# new_sheet.net
KiCad netlist of a schematic drawn in Altium Designer
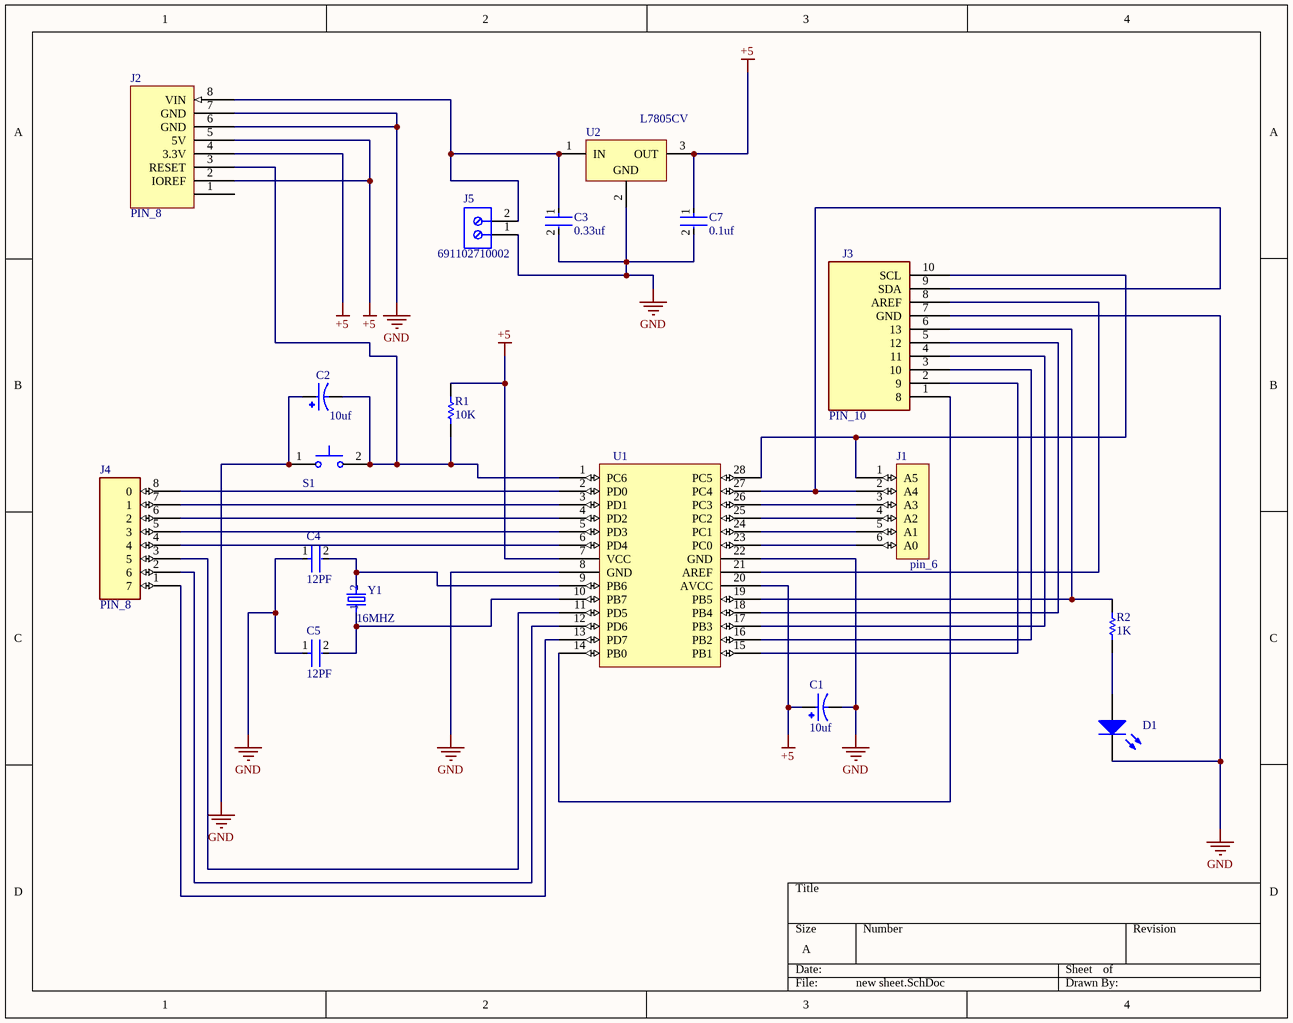
[diagram p0: new sheet.SchDoc]

(export (version "E")
  (design (tool "Eeschema 10.0.6"))
  (components
    (comp (ref "C1")
      (value "10uf")
      (footprint "PcbLib1:CAPPRD500W50D630H1120")
      (description "Cap Aluminum Lytic 10uF 100V 20% Radial 105C Automotive Ammo")
      (fields (field (name "MF") "Panasonic") (field (name "MP") "EEU-FC2A100B"))
      (libsource (lib "*") (part "EEUFC2A100B"))
    )
    (comp (ref "C2")
      (value "10uf")
      (footprint "PcbLib1:CAPPRD500W50D630H1120")
      (description "Cap Aluminum Lytic 10uF 100V 20% Radial 105C Automotive Ammo")
      (fields (field (name "MF") "Panasonic") (field (name "MP") "EEU-FC2A100B"))
      (libsource (lib "*") (part "EEUFC2A100B"))
    )
    (comp (ref "C3")
      (value "0.33uf")
      (footprint "FP-K15H5-MFG")
      (description "CAP CER 0.1UF 50V X7R RADIAL")
      (fields (field (name "TOLERANCE") "10%") (field (name "VOLTAGE") "50V"))
      (libsource (lib "Altium Content Vault") (part "02cd4be3c70576c341d710602a673aa"))
    )
    (comp (ref "C4")
      (value "12PF")
      (footprint "FP-K15H5-MFG")
      (description "CAP CER 0.1UF 50V X7R RADIAL")
      (fields (field (name "TOLERANCE") "10%") (field (name "VOLTAGE") "50V"))
      (libsource (lib "Altium Content Vault") (part "02cd4be3c70576c341d710602a673aa"))
    )
    (comp (ref "C5")
      (value "12PF")
      (footprint "FP-K15H5-MFG")
      (description "CAP CER 0.1UF 50V X7R RADIAL")
      (fields (field (name "TOLERANCE") "10%") (field (name "VOLTAGE") "50V"))
      (libsource (lib "Altium Content Vault") (part "02cd4be3c70576c341d710602a673aa"))
    )
    (comp (ref "C7")
      (value "0.1uf")
      (footprint "FP-K15H5-MFG")
      (description "CAP CER 0.1UF 50V X7R RADIAL")
      (fields (field (name "TOLERANCE") "10%") (field (name "VOLTAGE") "50V"))
      (libsource (lib "Altium Content Vault") (part "02cd4be3c70576c341d710602a673aa"))
    )
    (comp (ref "D1")
      (value "Light-Emitting Diode")
      (footprint "LED")
      (libsource (lib "Simulation Generic Components") (part "LED"))
    )
    (comp (ref "J1") (value "pin_6") (footprint "pin_6") (libsource (lib "*") (part "pin_6")))
    (comp (ref "J2") (value "PIN_8") (footprint "pin_8") (libsource (lib "*") (part "PIN_8")))
    (comp (ref "J3")
      (value "PIN_10")
      (footprint "pin_10")
      (fields
        (field (name "MANUFACTURER_PART_NUMBER") "22-23-2101")
        (field (name "MOUSER PART NUMBER") "538-22-23-2101")
      )
      (libsource (lib "*") (part "22-23-2101"))
    )
    (comp (ref "J4")
      (value "PIN_8")
      (footprint "pin_8")
      (description "Headers & Wire Housings 2.54MM PITCH SRSW T/H HEADER 8 CKT")
      (fields
        (field (name "MANUFACTURER_PART_NUMBER") "87891-0808")
        (field (name "MOUSER PART NUMBER") "538-87891-0808")
      )
      (libsource (lib "*") (part "PIN DIGITAL"))
    )
    (comp (ref "J5")
      (value "691102710002")
      (footprint "691102710002")
      (fields (field (name "VOLTAGE") "300V"))
      (libsource (lib "Altium Content Vault") (part "TBL - 1R - 02P - Screw"))
    )
    (comp (ref "R1")
      (value "10K")
      (footprint "RESISTANCE")
      (description "Resistor")
      (libsource (lib "Simulation Generic Components") (part "Resistor"))
    )
    (comp (ref "R2")
      (value "1K")
      (footprint "RESISTANCE")
      (description "Resistor")
      (libsource (lib "Simulation Generic Components") (part "Resistor"))
    )
    (comp (ref "S1")
      (value "~")
      (footprint "SW_BUTT-2")
      (description "Tactile Switches MINI PUSH BUTTON SWITCH 2-PIN QTY. 4")
      (fields (field (name "MF") "Gravitech") (field (name "MP") "BUTT-2"))
      (libsource (lib "*") (part "BUTT-2"))
    )
    (comp (ref "U1")
      (value "~")
      (footprint "DIP787W46P254L3467H508Q28")
      (libsource (lib "*") (part "atmega328p"))
    )
    (comp (ref "U2")
      (value "L7805CV")
      (footprint "TO220")
      (description "Positive Voltage Regulator, 5V, 3-Pin TO-220")
      (libsource (lib "Altium Content Vault") (part "PM-REG-L4940-SIL3"))
    )
    (comp (ref "Y1")
      (value "16MHZ")
      (footprint "XT9S20ANA16M")
      (description "Microprocessor, Crystal; 16 MHz; + 30 ppm _Typ._ @ 25 degC; 7 pF _Max._; 40 Ohm")
      (fields (field (name "MF") "Vishay Dale") (field (name "MP") "XT9S20ANA16M"))
      (libsource (lib "*") (part "XT9S20ANA16M"))
    )
  )
  (nets
    (net (code "1") (name "+5") (class "Default")
      (node (ref "C1") (pin "P") (pinfunction "P_P") (pintype "passive"))
      (node (ref "C7") (pin "1") (pinfunction "1_1") (pintype "passive"))
      (node (ref "J2") (pin "2") (pinfunction "IOREF_2") (pintype "power_in"))
      (node (ref "J2") (pin "4") (pinfunction "3.3V_4") (pintype "power_in"))
      (node (ref "J2") (pin "5") (pinfunction "5V_5") (pintype "power_in"))
      (node (ref "R1") (pin "2") (pinfunction "2_2") (pintype "passive"))
      (node (ref "U1") (pin "20") (pinfunction "AVCC_20") (pintype "power_in"))
      (node (ref "U1") (pin "7") (pinfunction "VCC_7") (pintype "power_in"))
      (node (ref "U2") (pin "3") (pinfunction "OUT_3") (pintype "power_in"))
    )
    (net (code "2") (name "GND") (class "Default")
      (node (ref "C1") (pin "N") (pinfunction "N_N") (pintype "passive"))
      (node (ref "C2") (pin "P") (pinfunction "P_P") (pintype "passive"))
      (node (ref "C3") (pin "2") (pinfunction "2_2") (pintype "passive"))
      (node (ref "C4") (pin "1") (pinfunction "1_1") (pintype "passive"))
      (node (ref "C5") (pin "1") (pinfunction "1_1") (pintype "passive"))
      (node (ref "C7") (pin "2") (pinfunction "2_2") (pintype "passive"))
      (node (ref "D1") (pin "2") (pinfunction "K_2") (pintype "passive"))
      (node (ref "J2") (pin "6") (pinfunction "GND_6") (pintype "power_in"))
      (node (ref "J2") (pin "7") (pinfunction "GND_7") (pintype "power_in"))
      (node (ref "J3") (pin "7") (pinfunction "GND_7") (pintype "passive"))
      (node (ref "J5") (pin "1") (pinfunction "1_1") (pintype "passive"))
      (node (ref "S1") (pin "1") (pinfunction "1_1") (pintype "passive"))
      (node (ref "U1") (pin "22") (pinfunction "GND_22") (pintype "power_in"))
      (node (ref "U1") (pin "8") (pinfunction "GND_8") (pintype "power_in"))
      (node (ref "U2") (pin "2") (pinfunction "GND_2") (pintype "power_in"))
    )
    (net (code "3") (name "Net-(D1-A)") (class "Default")
      (node (ref "D1") (pin "1") (pinfunction "A_1") (pintype "passive"))
      (node (ref "R2") (pin "1") (pinfunction "1_1") (pintype "passive"))
    )
    (net (code "4") (name "Net-(J1-A0)") (class "Default")
      (node (ref "J1") (pin "6") (pinfunction "A0_6") (pintype "bidirectional"))
      (node (ref "U1") (pin "23") (pinfunction "PC0_23") (pintype "bidirectional"))
    )
    (net (code "5") (name "Net-(J1-A1)") (class "Default")
      (node (ref "J1") (pin "5") (pinfunction "A1_5") (pintype "bidirectional"))
      (node (ref "U1") (pin "24") (pinfunction "PC1_24") (pintype "bidirectional"))
    )
    (net (code "6") (name "Net-(J1-A2)") (class "Default")
      (node (ref "J1") (pin "4") (pinfunction "A2_4") (pintype "bidirectional"))
      (node (ref "U1") (pin "25") (pinfunction "PC2_25") (pintype "bidirectional"))
    )
    (net (code "7") (name "Net-(J1-A3)") (class "Default")
      (node (ref "J1") (pin "3") (pinfunction "A3_3") (pintype "bidirectional"))
      (node (ref "U1") (pin "26") (pinfunction "PC3_26") (pintype "bidirectional"))
    )
    (net (code "8") (name "Net-(J1-A4)") (class "Default")
      (node (ref "J1") (pin "2") (pinfunction "A4_2") (pintype "bidirectional"))
      (node (ref "J3") (pin "9") (pinfunction "SDA_9") (pintype "passive"))
      (node (ref "U1") (pin "27") (pinfunction "PC4_27") (pintype "bidirectional"))
    )
    (net (code "9") (name "Net-(J1-A5)") (class "Default")
      (node (ref "J1") (pin "1") (pinfunction "A5_1") (pintype "bidirectional"))
      (node (ref "J3") (pin "10") (pinfunction "SCL_10") (pintype "passive"))
      (node (ref "U1") (pin "28") (pinfunction "PC5_28") (pintype "bidirectional"))
    )
    (net (code "10") (name "Net-(J2-RESET)") (class "Default")
      (node (ref "C2") (pin "N") (pinfunction "N_N") (pintype "passive"))
      (node (ref "J2") (pin "3") (pinfunction "RESET_3") (pintype "passive"))
      (node (ref "R1") (pin "1") (pinfunction "1_1") (pintype "passive"))
      (node (ref "S1") (pin "2") (pinfunction "2_2") (pintype "passive"))
      (node (ref "U1") (pin "1") (pinfunction "PC6_1") (pintype "bidirectional"))
    )
    (net (code "11") (name "Net-(J2-VIN)") (class "Default")
      (node (ref "C3") (pin "1") (pinfunction "1_1") (pintype "passive"))
      (node (ref "J2") (pin "8") (pinfunction "VIN_8") (pintype "input"))
      (node (ref "J5") (pin "2") (pinfunction "2_2") (pintype "passive"))
      (node (ref "U2") (pin "1") (pinfunction "IN_1") (pintype "power_in"))
    )
    (net (code "12") (name "Net-(J3-8)") (class "Default")
      (node (ref "J3") (pin "1") (pinfunction "8_1") (pintype "passive"))
      (node (ref "U1") (pin "14") (pinfunction "PB0_14") (pintype "bidirectional"))
    )
    (net (code "13") (name "Net-(J3-9)") (class "Default")
      (node (ref "J3") (pin "2") (pinfunction "9_2") (pintype "passive"))
      (node (ref "U1") (pin "15") (pinfunction "PB1_15") (pintype "bidirectional"))
    )
    (net (code "14") (name "Net-(J3-10)") (class "Default")
      (node (ref "J3") (pin "3") (pinfunction "10_3") (pintype "passive"))
      (node (ref "U1") (pin "16") (pinfunction "PB2_16") (pintype "bidirectional"))
    )
    (net (code "15") (name "Net-(J3-11)") (class "Default")
      (node (ref "J3") (pin "4") (pinfunction "11_4") (pintype "passive"))
      (node (ref "U1") (pin "17") (pinfunction "PB3_17") (pintype "bidirectional"))
    )
    (net (code "16") (name "Net-(J3-12)") (class "Default")
      (node (ref "J3") (pin "5") (pinfunction "12_5") (pintype "passive"))
      (node (ref "U1") (pin "18") (pinfunction "PB4_18") (pintype "bidirectional"))
    )
    (net (code "17") (name "Net-(J3-13)") (class "Default")
      (node (ref "J3") (pin "6") (pinfunction "13_6") (pintype "passive"))
      (node (ref "R2") (pin "2") (pinfunction "2_2") (pintype "passive"))
      (node (ref "U1") (pin "19") (pinfunction "PB5_19") (pintype "bidirectional"))
    )
    (net (code "18") (name "Net-(J3-AREF)") (class "Default")
      (node (ref "J3") (pin "8") (pinfunction "AREF_8") (pintype "passive"))
      (node (ref "U1") (pin "21") (pinfunction "AREF_21") (pintype "power_in"))
    )
    (net (code "19") (name "Net-(J4-0)") (class "Default")
      (node (ref "J4") (pin "8") (pinfunction "0_8") (pintype "bidirectional"))
      (node (ref "U1") (pin "2") (pinfunction "PD0_2") (pintype "bidirectional"))
    )
    (net (code "20") (name "Net-(J4-1)") (class "Default")
      (node (ref "J4") (pin "7") (pinfunction "1_7") (pintype "bidirectional"))
      (node (ref "U1") (pin "3") (pinfunction "PD1_3") (pintype "bidirectional"))
    )
    (net (code "21") (name "Net-(J4-2)") (class "Default")
      (node (ref "J4") (pin "6") (pinfunction "2_6") (pintype "bidirectional"))
      (node (ref "U1") (pin "4") (pinfunction "PD2_4") (pintype "bidirectional"))
    )
    (net (code "22") (name "Net-(J4-3)") (class "Default")
      (node (ref "J4") (pin "5") (pinfunction "3_5") (pintype "bidirectional"))
      (node (ref "U1") (pin "5") (pinfunction "PD3_5") (pintype "bidirectional"))
    )
    (net (code "23") (name "Net-(J4-5)") (class "Default")
      (node (ref "J4") (pin "3") (pinfunction "5_3") (pintype "bidirectional"))
      (node (ref "U1") (pin "11") (pinfunction "PD5_11") (pintype "bidirectional"))
    )
    (net (code "24") (name "Net-(J4-6)") (class "Default")
      (node (ref "J4") (pin "2") (pinfunction "6_2") (pintype "bidirectional"))
      (node (ref "U1") (pin "12") (pinfunction "PD6_12") (pintype "bidirectional"))
    )
    (net (code "25") (name "Net-(J4-7)") (class "Default")
      (node (ref "J4") (pin "1") (pinfunction "7_1") (pintype "bidirectional"))
      (node (ref "U1") (pin "13") (pinfunction "PD7_13") (pintype "bidirectional"))
    )
    (net (code "26") (name "Net-(U1-PB6)") (class "Default")
      (node (ref "C4") (pin "2") (pinfunction "2_2") (pintype "passive"))
      (node (ref "U1") (pin "9") (pinfunction "PB6_9") (pintype "bidirectional"))
      (node (ref "Y1") (pin "2") (pinfunction "2_2") (pintype "passive"))
    )
    (net (code "27") (name "Net-(U1-PB7)") (class "Default")
      (node (ref "C5") (pin "2") (pinfunction "2_2") (pintype "passive"))
      (node (ref "U1") (pin "10") (pinfunction "PB7_10") (pintype "bidirectional"))
      (node (ref "Y1") (pin "1") (pinfunction "1_1") (pintype "passive"))
    )
    (net (code "28") (name "Net-(U1-PD4)") (class "Default")
      (node (ref "J4") (pin "4") (pinfunction "4_4") (pintype "bidirectional"))
      (node (ref "U1") (pin "6") (pinfunction "PD4_6") (pintype "bidirectional"))
    )
    (net (code "29") (name "unconnected-(J2-Pad1)") (class "Default")
      (node (ref "J2") (pin "1") (pintype "passive"))
    )
  )
)
